# Controler-Board.net
KiCad netlist of a schematic drawn in EAGLE
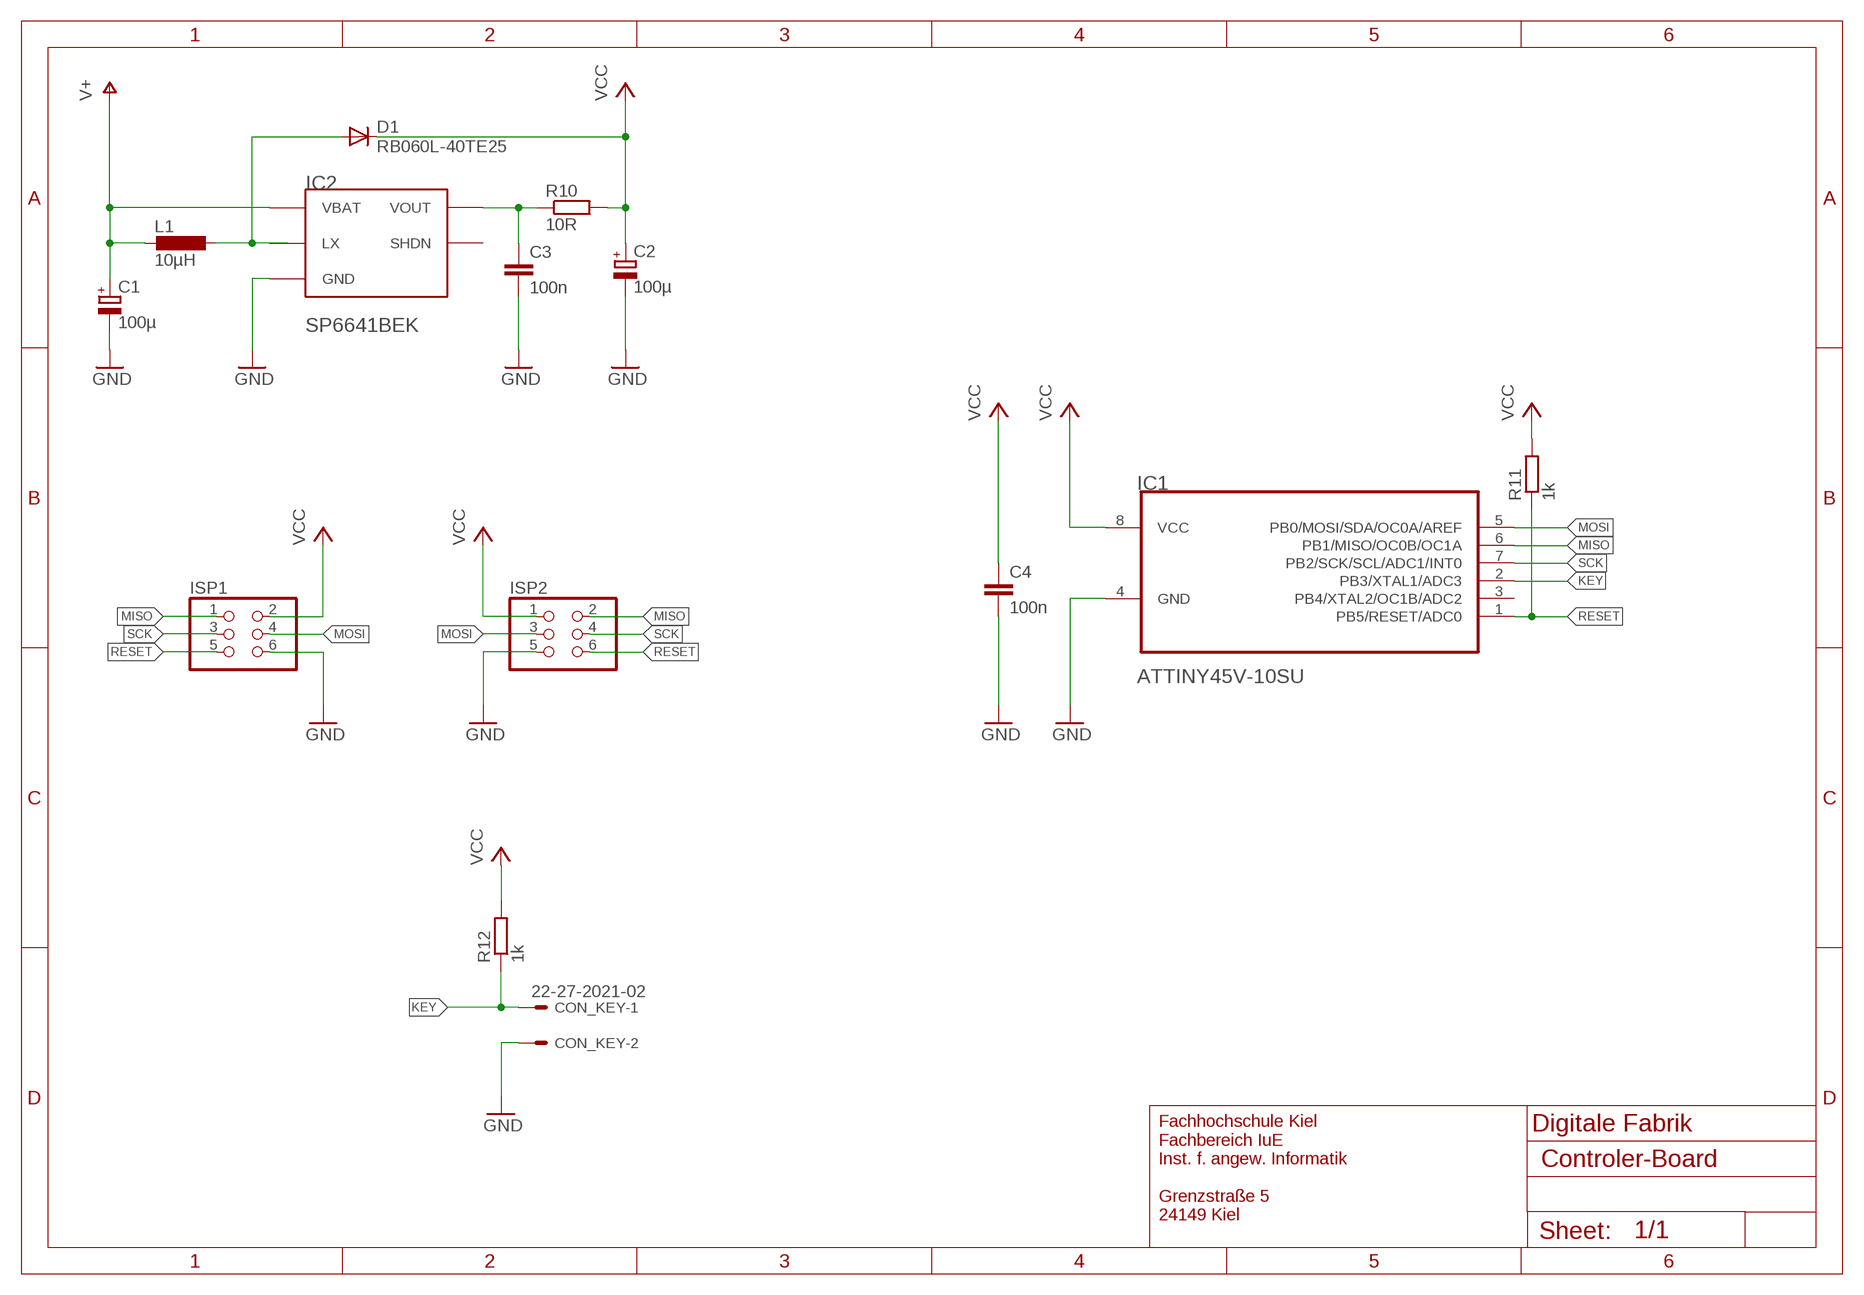
[diagram p0: schematic, sheet 1]

(export (version "E")
  (design (tool "Eeschema 10.0.6"))
  (components
    (comp (ref "C1")
      (value "100µ")
      (footprint "eagle-import:PANASONIC_C")
      (libsource (lib "eagle-import") (part "CPOL-EUC"))
    )
    (comp (ref "C2")
      (value "100µ")
      (footprint "eagle-import:PANASONIC_C")
      (libsource (lib "eagle-import") (part "CPOL-EUC"))
    )
    (comp (ref "C3")
      (value "100n")
      (footprint "eagle-import:C1206")
      (libsource (lib "eagle-import") (part "C-EUC1206"))
    )
    (comp (ref "C4")
      (value "100n")
      (footprint "eagle-import:C0805")
      (libsource (lib "eagle-import") (part "C-EUC0805"))
    )
    (comp (ref "CON_KEY")
      (value "22-27-2021-02")
      (footprint "eagle-import:6410-02")
      (libsource (lib "eagle-import") (part "22-?-0227-2021"))
    )
    (comp (ref "D1")
      (value "RB060L-40TE25")
      (footprint "eagle-import:SOD106-R")
      (libsource (lib "eagle-import") (part "DIODE-SOD106-R"))
    )
    (comp (ref "IC1")
      (value "ATTINY45V-10SU")
      (footprint "eagle-import:SOIC127P798X216-8N")
      (libsource (lib "eagle-import") (part "ATTINY45V-10SU"))
    )
    (comp (ref "IC2")
      (value "SP6641BEK")
      (footprint "eagle-import:SOT23-5")
      (libsource (lib "eagle-import") (part "SP6641BEK"))
    )
    (comp (ref "ISP1")
      (value "PINHD-2X03_2.54-SMD")
      (footprint "eagle-import:2X03SMD")
      (libsource (lib "eagle-import") (part "PINHD-2X03_2.54-SMD"))
    )
    (comp (ref "ISP2")
      (value "PINHD-2X03_2.54-SMD")
      (footprint "eagle-import:2X03SMD")
      (libsource (lib "eagle-import") (part "PINHD-2X03_2.54-SMD"))
    )
    (comp (ref "L1")
      (value "10µH")
      (footprint "eagle-import:R1206")
      (libsource (lib "eagle-import") (part "L-EUL1206"))
    )
    (comp (ref "R10")
      (value "10R")
      (footprint "eagle-import:R0805")
      (libsource (lib "eagle-import") (part "R-EU_R0805"))
    )
    (comp (ref "R11")
      (value "1k")
      (footprint "eagle-import:R0805")
      (libsource (lib "eagle-import") (part "R-EU_R0805"))
    )
    (comp (ref "R12")
      (value "1k")
      (footprint "eagle-import:R0805")
      (libsource (lib "eagle-import") (part "R-EU_R0805"))
    )
  )
  (nets
    (net (code "1") (name "GND") (class "Default")
      (node (ref "C1") (pin "-") (pinfunction "-_-") (pintype "passive"))
      (node (ref "C2") (pin "-") (pinfunction "-_-") (pintype "passive"))
      (node (ref "C3") (pin "2") (pinfunction "2_2") (pintype "passive"))
      (node (ref "C4") (pin "2") (pinfunction "2_2") (pintype "passive"))
      (node (ref "CON_KEY") (pin "2") (pinfunction "S_2") (pintype "passive"))
      (node (ref "IC1") (pin "4") (pinfunction "GND_4") (pintype "passive"))
      (node (ref "IC2") (pin "2") (pinfunction "GND_2") (pintype "output"))
      (node (ref "ISP1") (pin "6") (pinfunction "6_6") (pintype "passive"))
      (node (ref "ISP2") (pin "5") (pinfunction "5_5") (pintype "passive"))
    )
    (net (code "2") (name "KEY") (class "Default")
      (node (ref "CON_KEY") (pin "1") (pinfunction "S_1") (pintype "passive"))
      (node (ref "IC1") (pin "2") (pinfunction "PB3/XTAL1/ADC3_2") (pintype "bidirectional"))
      (node (ref "R12") (pin "1") (pinfunction "1_1") (pintype "passive"))
    )
    (net (code "3") (name "MISO") (class "Default")
      (node (ref "IC1") (pin "6") (pinfunction "PB1/MISO/OC0B/OC1A_6") (pintype "bidirectional"))
      (node (ref "ISP1") (pin "1") (pinfunction "1_1") (pintype "passive"))
      (node (ref "ISP2") (pin "2") (pinfunction "2_2") (pintype "passive"))
    )
    (net (code "4") (name "MOSI") (class "Default")
      (node (ref "IC1") (pin "5") (pinfunction "PB0/MOSI/SDA/OC0A/AREF_5") (pintype "bidirectional"))
      (node (ref "ISP1") (pin "4") (pinfunction "4_4") (pintype "passive"))
      (node (ref "ISP2") (pin "3") (pinfunction "3_3") (pintype "passive"))
    )
    (net (code "5") (name "Net-(D1-PadA)") (class "Default")
      (node (ref "D1") (pin "A") (pinfunction "A_A") (pintype "passive"))
      (node (ref "L1") (pin "1") (pinfunction "1_1") (pintype "passive"))
    )
    (net (code "6") (name "Net-(IC2-VOUT)") (class "Default")
      (node (ref "C3") (pin "1") (pinfunction "1_1") (pintype "passive"))
      (node (ref "IC2") (pin "3") (pinfunction "VOUT_3") (pintype "output"))
      (node (ref "R10") (pin "1") (pinfunction "1_1") (pintype "passive"))
    )
    (net (code "7") (name "RESET") (class "Default")
      (node (ref "IC1") (pin "1") (pinfunction "PB5/RESET/ADC0_1") (pintype "bidirectional"))
      (node (ref "ISP1") (pin "5") (pinfunction "5_5") (pintype "passive"))
      (node (ref "ISP2") (pin "6") (pinfunction "6_6") (pintype "passive"))
      (node (ref "R11") (pin "1") (pinfunction "1_1") (pintype "passive"))
    )
    (net (code "8") (name "SCK") (class "Default")
      (node (ref "IC1") (pin "7") (pinfunction "PB2/SCK/SCL/ADC1/INT0_7") (pintype "bidirectional"))
      (node (ref "ISP1") (pin "3") (pinfunction "3_3") (pintype "passive"))
      (node (ref "ISP2") (pin "4") (pinfunction "4_4") (pintype "passive"))
    )
    (net (code "9") (name "V+") (class "Default")
      (node (ref "C1") (pin "+") (pinfunction "+_+") (pintype "passive"))
      (node (ref "IC2") (pin "5") (pinfunction "VBAT_5") (pintype "output"))
      (node (ref "L1") (pin "2") (pinfunction "2_2") (pintype "passive"))
    )
    (net (code "10") (name "VCC") (class "Default")
      (node (ref "C2") (pin "+") (pinfunction "+_+") (pintype "passive"))
      (node (ref "C4") (pin "1") (pinfunction "1_1") (pintype "passive"))
      (node (ref "D1") (pin "C") (pinfunction "C_C") (pintype "passive"))
      (node (ref "IC1") (pin "8") (pinfunction "VCC_8") (pintype "power_in"))
      (node (ref "ISP1") (pin "2") (pinfunction "2_2") (pintype "passive"))
      (node (ref "ISP2") (pin "1") (pinfunction "1_1") (pintype "passive"))
      (node (ref "R10") (pin "2") (pinfunction "2_2") (pintype "passive"))
      (node (ref "R11") (pin "2") (pinfunction "2_2") (pintype "passive"))
      (node (ref "R12") (pin "2") (pinfunction "2_2") (pintype "passive"))
    )
    (net (code "11") (name "unconnected-(IC1-PB4{slash}XTAL2{slash}OC1B{slash}ADC2-Pad3)") (class "Default")
      (node (ref "IC1") (pin "3") (pinfunction "PB4/XTAL2/OC1B/ADC2_3") (pintype "bidirectional"))
    )
    (net (code "12") (name "unconnected-(IC2-LX-Pad1)") (class "Default")
      (node (ref "IC2") (pin "1") (pinfunction "LX_1") (pintype "output"))
    )
    (net (code "13") (name "unconnected-(IC2-SHDN-Pad4)") (class "Default")
      (node (ref "IC2") (pin "4") (pinfunction "SHDN_4") (pintype "output"))
    )
  )
)
